# Meas_Channel.net
KiCad netlist of a schematic drawn in Altium Designer
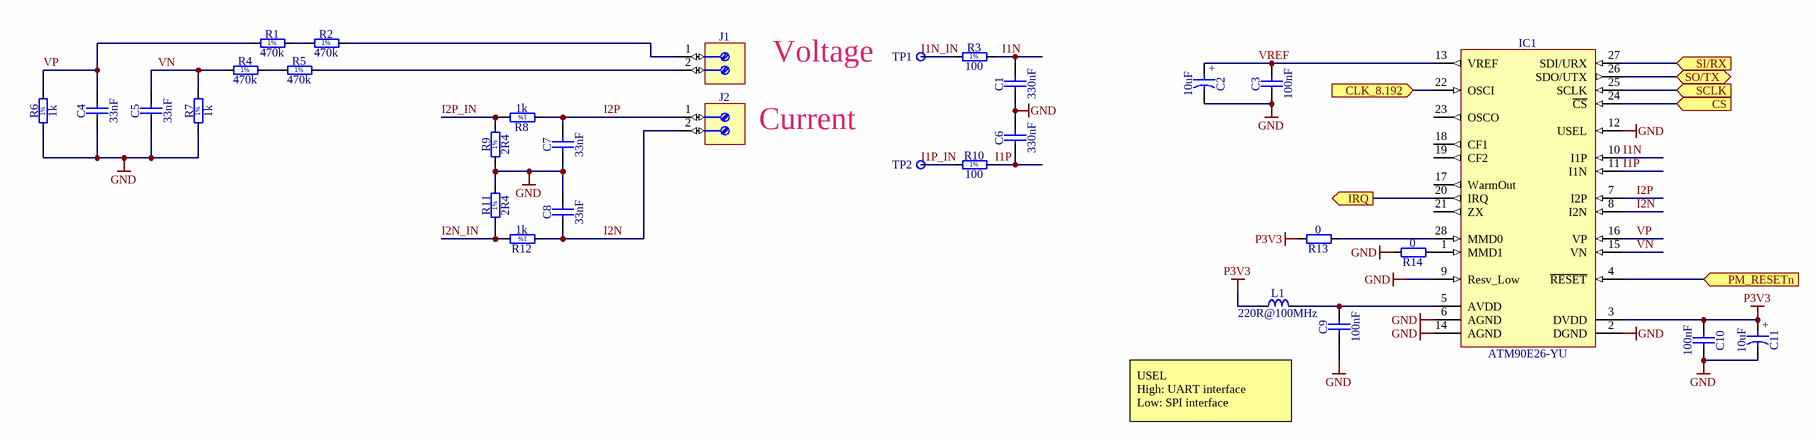
[diagram p0: Meas_Channel.SchDoc]

(export (version "E")
  (design (tool "Eeschema 10.0.6"))
  (components
    (comp (ref "C1")
      (value "330nF")
      (footprint "CAPC1608X87N")
      (description "Non-polarised capacitor")
      (fields
        (field (name "PART NUMBER") "CC0603_330NF_16V_10%_X5R")
        (field (name "VOLTAGE") "16V")
        (field (name "AUTHOR") "CERN DEM JLC")
      )
      (libsource (lib "Capacitors") (part "Capacitor - non polarized"))
    )
    (comp (ref "C2")
      (value "10uF")
      (footprint "CAPMP3216X180N")
      (description "Polarised capacitor")
      (fields
        (field (name "PART NUMBER") "CTE3216-18_10UF_16V_20%_AVX_TCJ")
        (field (name "VOLTAGE") "16V")
        (field (name "AUTHOR") "CERN DEM JLC")
      )
      (libsource (lib "Capacitors") (part "Capacitor - polarized"))
    )
    (comp (ref "C3")
      (value "100nF")
      (footprint "CAPC1005X55N")
      (description "Non-polarised capacitor")
      (fields
        (field (name "PART NUMBER") "CC0402_100NF_16V_10%_X5R")
        (field (name "VOLTAGE") "16V")
        (field (name "AUTHOR") "CERN DEM JLC")
      )
      (libsource (lib "Capacitors") (part "Capacitor - non polarized"))
    )
    (comp (ref "C4")
      (value "33nF")
      (footprint "CAPC1005X55N")
      (description "Non-polarised capacitor")
      (fields
        (field (name "PART NUMBER") "CC0402_33NF_16V_10%_X7R")
        (field (name "VOLTAGE") "16V")
        (field (name "AUTHOR") "CERN DEM JLC")
      )
      (libsource (lib "Capacitors") (part "Capacitor - non polarized"))
    )
    (comp (ref "C5")
      (value "33nF")
      (footprint "CAPC1005X55N")
      (description "Non-polarised capacitor")
      (fields
        (field (name "PART NUMBER") "CC0402_33NF_16V_10%_X7R")
        (field (name "VOLTAGE") "16V")
        (field (name "AUTHOR") "CERN DEM JLC")
      )
      (libsource (lib "Capacitors") (part "Capacitor - non polarized"))
    )
    (comp (ref "C6")
      (value "330nF")
      (footprint "CAPC1608X87N")
      (description "Non-polarised capacitor")
      (fields
        (field (name "PART NUMBER") "CC0603_330NF_16V_10%_X5R")
        (field (name "VOLTAGE") "16V")
        (field (name "AUTHOR") "CERN DEM JLC")
      )
      (libsource (lib "Capacitors") (part "Capacitor - non polarized"))
    )
    (comp (ref "C7")
      (value "33nF")
      (footprint "CAPC1005X55N")
      (description "Non-polarised capacitor")
      (fields
        (field (name "PART NUMBER") "CC0402_33NF_16V_10%_X7R")
        (field (name "VOLTAGE") "16V")
        (field (name "AUTHOR") "CERN DEM JLC")
      )
      (libsource (lib "Capacitors") (part "Capacitor - non polarized"))
    )
    (comp (ref "C8")
      (value "33nF")
      (footprint "CAPC1005X55N")
      (description "Non-polarised capacitor")
      (fields
        (field (name "PART NUMBER") "CC0402_33NF_16V_10%_X7R")
        (field (name "VOLTAGE") "16V")
        (field (name "AUTHOR") "CERN DEM JLC")
      )
      (libsource (lib "Capacitors") (part "Capacitor - non polarized"))
    )
    (comp (ref "C9")
      (value "100nF")
      (footprint "CAPC1005X55N")
      (description "Non-polarised capacitor")
      (fields
        (field (name "PART NUMBER") "CC0402_100NF_16V_10%_X5R")
        (field (name "VOLTAGE") "16V")
        (field (name "AUTHOR") "CERN DEM JLC")
      )
      (libsource (lib "Capacitors") (part "Capacitor - non polarized"))
    )
    (comp (ref "C10")
      (value "100nF")
      (footprint "CAPC1005X55N")
      (description "Non-polarised capacitor")
      (fields
        (field (name "PART NUMBER") "CC0402_100NF_16V_10%_X5R")
        (field (name "VOLTAGE") "16V")
        (field (name "AUTHOR") "CERN DEM JLC")
      )
      (libsource (lib "Capacitors") (part "Capacitor - non polarized"))
    )
    (comp (ref "C11")
      (value "10uF")
      (footprint "CAPMP3216X180N")
      (description "Polarised capacitor")
      (fields
        (field (name "PART NUMBER") "CTE3216-18_10UF_16V_20%_AVX_TCJ")
        (field (name "VOLTAGE") "16V")
        (field (name "AUTHOR") "CERN DEM JLC")
      )
      (libsource (lib "Capacitors") (part "Capacitor - polarized"))
    )
    (comp (ref "IC1")
      (value "ATM90E26-YU")
      (footprint "SOP65P780X200-28N")
      (description "Single-Phase High-Performance Wide-Span, Energy Metering IC")
      (fields (field (name "MANUFACTURER") "MICROCHIP TECHNOLOGY") (field (name "AUTHOR") "CERN DEM MR"))
      (libsource (lib "ICs And Semiconductors") (part "ATM90E26-YU"))
    )
    (comp (ref "J1")
      (value "~")
      (footprint "PHOENIX_1751248")
      (description "Terminal Block, 2 Positions, Screw Connection")
      (fields
        (field (name "PART NUMBER") "PHOENIX_1751248")
        (field (name "MANUFACTURER") "PHOENIX CONTACT")
        (field (name "AUTHOR") "CERN DEM JLC")
      )
      (libsource (lib "Connectors") (part "Terminal Block_2 Positions_Screw Connection"))
    )
    (comp (ref "J2")
      (value "~")
      (footprint "PHOENIX_1725656")
      (description "Terminal Block, 2 Positions, Screw Connection")
      (fields
        (field (name "PART NUMBER") "PHOENIX_1725656")
        (field (name "MANUFACTURER") "PHOENIX CONTACT")
        (field (name "AUTHOR") "CERN DEM JMW")
      )
      (libsource (lib "Connectors") (part "Terminal Block_2 Positions_Screw Connection"))
    )
    (comp (ref "L1")
      (value "220R@100MHz")
      (footprint "INDC1005X55N")
      (description "Inductor")
      (fields
        (field (name "PART NUMBER") "IND0402_MURATA_BLM15HB221SN1")
        (field (name "POWER") "250mA")
        (field (name "AUTHOR") "CERN DEM JLC")
      )
      (libsource (lib "Inductors & Transformers") (part "Inductor"))
    )
    (comp (ref "R1")
      (value "470k")
      (footprint "RESC3216X65N")
      (description "Resistor - 1%")
      (fields
        (field (name "PART NUMBER") "R1206_470K_1%_0.25W_100PPM")
        (field (name "POWER") "0.25W")
        (field (name "AUTHOR") "CERN DEM JLC")
      )
      (libsource (lib "Resistors") (part "Resistor - 1%"))
    )
    (comp (ref "R2")
      (value "470k")
      (footprint "RESC3216X65N")
      (description "Resistor - 1%")
      (fields
        (field (name "PART NUMBER") "R1206_470K_1%_0.25W_100PPM")
        (field (name "POWER") "0.25W")
        (field (name "AUTHOR") "CERN DEM JLC")
      )
      (libsource (lib "Resistors") (part "Resistor - 1%"))
    )
    (comp (ref "R3")
      (value "100")
      (footprint "RESC1005X40N")
      (description "Resistor - 1%")
      (fields
        (field (name "PART NUMBER") "R0402_100R_1%_0.0625W_100PPM")
        (field (name "POWER") "0.0625W")
        (field (name "AUTHOR") "CERN DEM JLC")
      )
      (libsource (lib "Resistors") (part "Resistor - 1%"))
    )
    (comp (ref "R4")
      (value "470k")
      (footprint "RESC3216X65N")
      (description "Resistor - 1%")
      (fields
        (field (name "PART NUMBER") "R1206_470K_1%_0.25W_100PPM")
        (field (name "POWER") "0.25W")
        (field (name "AUTHOR") "CERN DEM JLC")
      )
      (libsource (lib "Resistors") (part "Resistor - 1%"))
    )
    (comp (ref "R5")
      (value "470k")
      (footprint "RESC3216X65N")
      (description "Resistor - 1%")
      (fields
        (field (name "PART NUMBER") "R1206_470K_1%_0.25W_100PPM")
        (field (name "POWER") "0.25W")
        (field (name "AUTHOR") "CERN DEM JLC")
      )
      (libsource (lib "Resistors") (part "Resistor - 1%"))
    )
    (comp (ref "R6")
      (value "1k")
      (footprint "RESC1005X40N")
      (description "Resistor - 1%")
      (fields
        (field (name "PART NUMBER") "R0402_1K_1%_0.0625W_100PPM")
        (field (name "POWER") "0.0625W")
        (field (name "AUTHOR") "CERN DEM JLC")
      )
      (libsource (lib "Resistors") (part "Resistor - 1%"))
    )
    (comp (ref "R7")
      (value "1k")
      (footprint "RESC1005X40N")
      (description "Resistor - 1%")
      (fields
        (field (name "PART NUMBER") "R0402_1K_1%_0.0625W_100PPM")
        (field (name "POWER") "0.0625W")
        (field (name "AUTHOR") "CERN DEM JLC")
      )
      (libsource (lib "Resistors") (part "Resistor - 1%"))
    )
    (comp (ref "R8")
      (value "1k")
      (footprint "RESC1005X40N")
      (description "Resistor - 1%")
      (fields
        (field (name "PART NUMBER") "R0402_1K_1%_0.0625W_100PPM")
        (field (name "POWER") "0.0625W")
        (field (name "AUTHOR") "CERN DEM JLC")
      )
      (libsource (lib "Resistors") (part "Resistor - 1%"))
    )
    (comp (ref "R9")
      (value "2R4")
      (footprint "RESC1608X55N")
      (description "Resistor - 1%")
      (fields
        (field (name "PART NUMBER") "R0603_2R4_1%_0.1W_200PPM")
        (field (name "POWER") "0.1W")
        (field (name "AUTHOR") "CERN DEM JLC")
      )
      (libsource (lib "Resistors") (part "Resistor - 1%"))
    )
    (comp (ref "R10")
      (value "100")
      (footprint "RESC1005X40N")
      (description "Resistor - 1%")
      (fields
        (field (name "PART NUMBER") "R0402_100R_1%_0.0625W_100PPM")
        (field (name "POWER") "0.0625W")
        (field (name "AUTHOR") "CERN DEM JLC")
      )
      (libsource (lib "Resistors") (part "Resistor - 1%"))
    )
    (comp (ref "R11")
      (value "2R4")
      (footprint "RESC1608X55N")
      (description "Resistor - 1%")
      (fields
        (field (name "PART NUMBER") "R0603_2R4_1%_0.1W_200PPM")
        (field (name "POWER") "0.1W")
        (field (name "AUTHOR") "CERN DEM JLC")
      )
      (libsource (lib "Resistors") (part "Resistor - 1%"))
    )
    (comp (ref "R12")
      (value "1k")
      (footprint "RESC1005X40N")
      (description "Resistor - 1%")
      (fields
        (field (name "PART NUMBER") "R0402_1K_1%_0.0625W_100PPM")
        (field (name "POWER") "0.0625W")
        (field (name "AUTHOR") "CERN DEM JLC")
      )
      (libsource (lib "Resistors") (part "Resistor - 1%"))
    )
    (comp (ref "R13")
      (value "0")
      (footprint "RESC1005X40N")
      (description "Resistor")
      (fields
        (field (name "PART NUMBER") "R0402_0R_JUMPER")
        (field (name "MANUFACTURER") "GENERIC")
        (field (name "AUTHOR") "CERN DEM JLC")
      )
      (libsource (lib "Resistors") (part "Resistor"))
    )
    (comp (ref "R14")
      (value "0")
      (footprint "RESC1005X40N")
      (description "Resistor")
      (fields
        (field (name "PART NUMBER") "R0402_0R_JUMPER")
        (field (name "MANUFACTURER") "GENERIC")
        (field (name "AUTHOR") "CERN DEM JLC")
      )
      (libsource (lib "Resistors") (part "Resistor"))
    )
    (comp (ref "TP1")
      (value "Test Point")
      (footprint "TPS127")
      (fields (field (name "PART NUMBER") "SMD_PAD_1.27X1.27MM") (field (name "AUTHOR") "CERN DEM JLC"))
      (libsource (lib "Eletro-mechanical") (part "Test Point"))
    )
    (comp (ref "TP2")
      (value "Test Point")
      (footprint "TPS127")
      (fields (field (name "PART NUMBER") "SMD_PAD_1.27X1.27MM") (field (name "AUTHOR") "CERN DEM JLC"))
      (libsource (lib "Eletro-mechanical") (part "Test Point"))
    )
  )
  (nets
    (net (code "1") (name "/CLK_8.192") (class "Default")
      (node (ref "IC1") (pin "22") (pinfunction "OSCI_22") (pintype "input"))
    )
    (net (code "2") (name "/CS") (class "Default")
      (node (ref "IC1") (pin "24") (pinfunction "~{CS}_24") (pintype "input"))
    )
    (net (code "3") (name "/I1N") (class "Default")
      (node (ref "C1") (pin "2") (pinfunction "2_2") (pintype "passive"))
      (node (ref "IC1") (pin "10") (pinfunction "I1P_10") (pintype "input"))
      (node (ref "R3") (pin "2") (pinfunction "2_2") (pintype "passive"))
    )
    (net (code "4") (name "/I1N_IN") (class "Default")
      (node (ref "R3") (pin "1") (pinfunction "1_1") (pintype "passive"))
      (node (ref "TP1") (pin "1") (pinfunction "1_1") (pintype "bidirectional"))
    )
    (net (code "5") (name "/I1P") (class "Default")
      (node (ref "C6") (pin "1") (pinfunction "1_1") (pintype "passive"))
      (node (ref "IC1") (pin "11") (pinfunction "I1N_11") (pintype "input"))
      (node (ref "R10") (pin "2") (pinfunction "2_2") (pintype "passive"))
    )
    (net (code "6") (name "/I1P_IN") (class "Default")
      (node (ref "R10") (pin "1") (pinfunction "1_1") (pintype "passive"))
      (node (ref "TP2") (pin "1") (pinfunction "1_1") (pintype "bidirectional"))
    )
    (net (code "7") (name "/I2N") (class "Default")
      (node (ref "C8") (pin "1") (pinfunction "1_1") (pintype "passive"))
      (node (ref "IC1") (pin "8") (pinfunction "I2N_8") (pintype "input"))
      (node (ref "J2") (pin "2") (pinfunction "2_2") (pintype "bidirectional"))
      (node (ref "R12") (pin "1") (pinfunction "1_1") (pintype "passive"))
    )
    (net (code "8") (name "/I2N_IN") (class "Default")
      (node (ref "R11") (pin "1") (pinfunction "1_1") (pintype "passive"))
      (node (ref "R12") (pin "2") (pinfunction "2_2") (pintype "passive"))
    )
    (net (code "9") (name "/I2P") (class "Default")
      (node (ref "C7") (pin "2") (pinfunction "2_2") (pintype "passive"))
      (node (ref "IC1") (pin "7") (pinfunction "I2P_7") (pintype "input"))
      (node (ref "J2") (pin "1") (pinfunction "1_1") (pintype "bidirectional"))
      (node (ref "R8") (pin "1") (pinfunction "1_1") (pintype "passive"))
    )
    (net (code "10") (name "/I2P_IN") (class "Default")
      (node (ref "R8") (pin "2") (pinfunction "2_2") (pintype "passive"))
      (node (ref "R9") (pin "2") (pinfunction "2_2") (pintype "passive"))
    )
    (net (code "11") (name "/IRQ") (class "Default")
      (node (ref "IC1") (pin "20") (pinfunction "IRQ_20") (pintype "output"))
    )
    (net (code "12") (name "/PM_RESETn") (class "Default")
      (node (ref "IC1") (pin "4") (pinfunction "~{RESET}_4") (pintype "input"))
    )
    (net (code "13") (name "/SCLK") (class "Default")
      (node (ref "IC1") (pin "25") (pinfunction "SCLK_25") (pintype "input"))
    )
    (net (code "14") (name "/SI{slash}RX") (class "Default")
      (node (ref "IC1") (pin "27") (pinfunction "SDI/URX_27") (pintype "input"))
    )
    (net (code "15") (name "/SO{slash}TX") (class "Default")
      (node (ref "IC1") (pin "26") (pinfunction "SDO/UTX_26") (pintype "output"))
    )
    (net (code "16") (name "/VN") (class "Default")
      (node (ref "C5") (pin "2") (pinfunction "2_2") (pintype "passive"))
      (node (ref "IC1") (pin "15") (pinfunction "VN_15") (pintype "input"))
      (node (ref "R4") (pin "1") (pinfunction "1_1") (pintype "passive"))
      (node (ref "R7") (pin "2") (pinfunction "2_2") (pintype "passive"))
    )
    (net (code "17") (name "/VP") (class "Default")
      (node (ref "C4") (pin "2") (pinfunction "2_2") (pintype "passive"))
      (node (ref "IC1") (pin "16") (pinfunction "VP_16") (pintype "input"))
      (node (ref "R1") (pin "1") (pinfunction "1_1") (pintype "passive"))
      (node (ref "R6") (pin "2") (pinfunction "2_2") (pintype "passive"))
    )
    (net (code "18") (name "/VREF") (class "Default")
      (node (ref "C2") (pin "1") (pinfunction "1_1") (pintype "passive"))
      (node (ref "C3") (pin "2") (pinfunction "2_2") (pintype "passive"))
      (node (ref "IC1") (pin "13") (pinfunction "VREF_13") (pintype "output"))
    )
    (net (code "19") (name "GND") (class "Default")
      (node (ref "C1") (pin "1") (pinfunction "1_1") (pintype "passive"))
      (node (ref "C10") (pin "2") (pinfunction "2_2") (pintype "passive"))
      (node (ref "C11") (pin "2") (pinfunction "2_2") (pintype "passive"))
      (node (ref "C2") (pin "2") (pinfunction "2_2") (pintype "passive"))
      (node (ref "C3") (pin "1") (pinfunction "1_1") (pintype "passive"))
      (node (ref "C4") (pin "1") (pinfunction "1_1") (pintype "passive"))
      (node (ref "C5") (pin "1") (pinfunction "1_1") (pintype "passive"))
      (node (ref "C6") (pin "2") (pinfunction "2_2") (pintype "passive"))
      (node (ref "C7") (pin "1") (pinfunction "1_1") (pintype "passive"))
      (node (ref "C8") (pin "2") (pinfunction "2_2") (pintype "passive"))
      (node (ref "C9") (pin "1") (pinfunction "1_1") (pintype "passive"))
      (node (ref "IC1") (pin "12") (pinfunction "USEL_12") (pintype "input"))
      (node (ref "IC1") (pin "14") (pinfunction "AGND_14") (pintype "power_in"))
      (node (ref "IC1") (pin "2") (pinfunction "DGND_2") (pintype "power_in"))
      (node (ref "IC1") (pin "6") (pinfunction "AGND_6") (pintype "power_in"))
      (node (ref "IC1") (pin "9") (pinfunction "Resv_Low_9") (pintype "input"))
      (node (ref "R11") (pin "2") (pinfunction "2_2") (pintype "passive"))
      (node (ref "R14") (pin "2") (pinfunction "2_2") (pintype "passive"))
      (node (ref "R6") (pin "1") (pinfunction "1_1") (pintype "passive"))
      (node (ref "R7") (pin "1") (pinfunction "1_1") (pintype "passive"))
      (node (ref "R9") (pin "1") (pinfunction "1_1") (pintype "passive"))
    )
    (net (code "20") (name "Net-(IC1-AVDD)") (class "Default")
      (node (ref "C9") (pin "2") (pinfunction "2_2") (pintype "passive"))
      (node (ref "IC1") (pin "5") (pinfunction "AVDD_5") (pintype "power_in"))
      (node (ref "L1") (pin "2") (pinfunction "2_2") (pintype "passive"))
    )
    (net (code "21") (name "Net-(IC1-MMD0)") (class "Default")
      (node (ref "IC1") (pin "28") (pinfunction "MMD0_28") (pintype "input"))
      (node (ref "R13") (pin "1") (pinfunction "1_1") (pintype "passive"))
    )
    (net (code "22") (name "Net-(IC1-MMD1)") (class "Default")
      (node (ref "IC1") (pin "1") (pinfunction "MMD1_1") (pintype "input"))
      (node (ref "R14") (pin "1") (pinfunction "1_1") (pintype "passive"))
    )
    (net (code "23") (name "Net-(J1-Pad1)") (class "Default")
      (node (ref "J1") (pin "1") (pinfunction "1_1") (pintype "bidirectional"))
      (node (ref "R2") (pin "2") (pinfunction "2_2") (pintype "passive"))
    )
    (net (code "24") (name "Net-(J1-Pad2)") (class "Default")
      (node (ref "J1") (pin "2") (pinfunction "2_2") (pintype "bidirectional"))
      (node (ref "R5") (pin "2") (pinfunction "2_2") (pintype "passive"))
    )
    (net (code "25") (name "Net-(R1-Pad2)") (class "Default")
      (node (ref "R1") (pin "2") (pinfunction "2_2") (pintype "passive"))
      (node (ref "R2") (pin "1") (pinfunction "1_1") (pintype "passive"))
    )
    (net (code "26") (name "Net-(R4-Pad2)") (class "Default")
      (node (ref "R4") (pin "2") (pinfunction "2_2") (pintype "passive"))
      (node (ref "R5") (pin "1") (pinfunction "1_1") (pintype "passive"))
    )
    (net (code "27") (name "P3V3") (class "Default")
      (node (ref "C10") (pin "1") (pinfunction "1_1") (pintype "passive"))
      (node (ref "C11") (pin "1") (pinfunction "1_1") (pintype "passive"))
      (node (ref "IC1") (pin "3") (pinfunction "DVDD_3") (pintype "power_in"))
      (node (ref "L1") (pin "1") (pinfunction "1_1") (pintype "passive"))
      (node (ref "R13") (pin "2") (pinfunction "2_2") (pintype "passive"))
    )
    (net (code "28") (name "unconnected-(IC1-CF1-Pad18)") (class "Default")
      (node (ref "IC1") (pin "18") (pinfunction "CF1_18") (pintype "output"))
    )
    (net (code "29") (name "unconnected-(IC1-CF2-Pad19)") (class "Default")
      (node (ref "IC1") (pin "19") (pinfunction "CF2_19") (pintype "output"))
    )
    (net (code "30") (name "unconnected-(IC1-OSCO-Pad23)") (class "Default")
      (node (ref "IC1") (pin "23") (pinfunction "OSCO_23") (pintype "output"))
    )
    (net (code "31") (name "unconnected-(IC1-WarmOut-Pad17)") (class "Default")
      (node (ref "IC1") (pin "17") (pinfunction "WarmOut_17") (pintype "output"))
    )
    (net (code "32") (name "unconnected-(IC1-ZX-Pad21)") (class "Default")
      (node (ref "IC1") (pin "21") (pinfunction "ZX_21") (pintype "output"))
    )
  )
)
